# powerboard_monitor.net
KiCad netlist of a schematic drawn in EAGLE
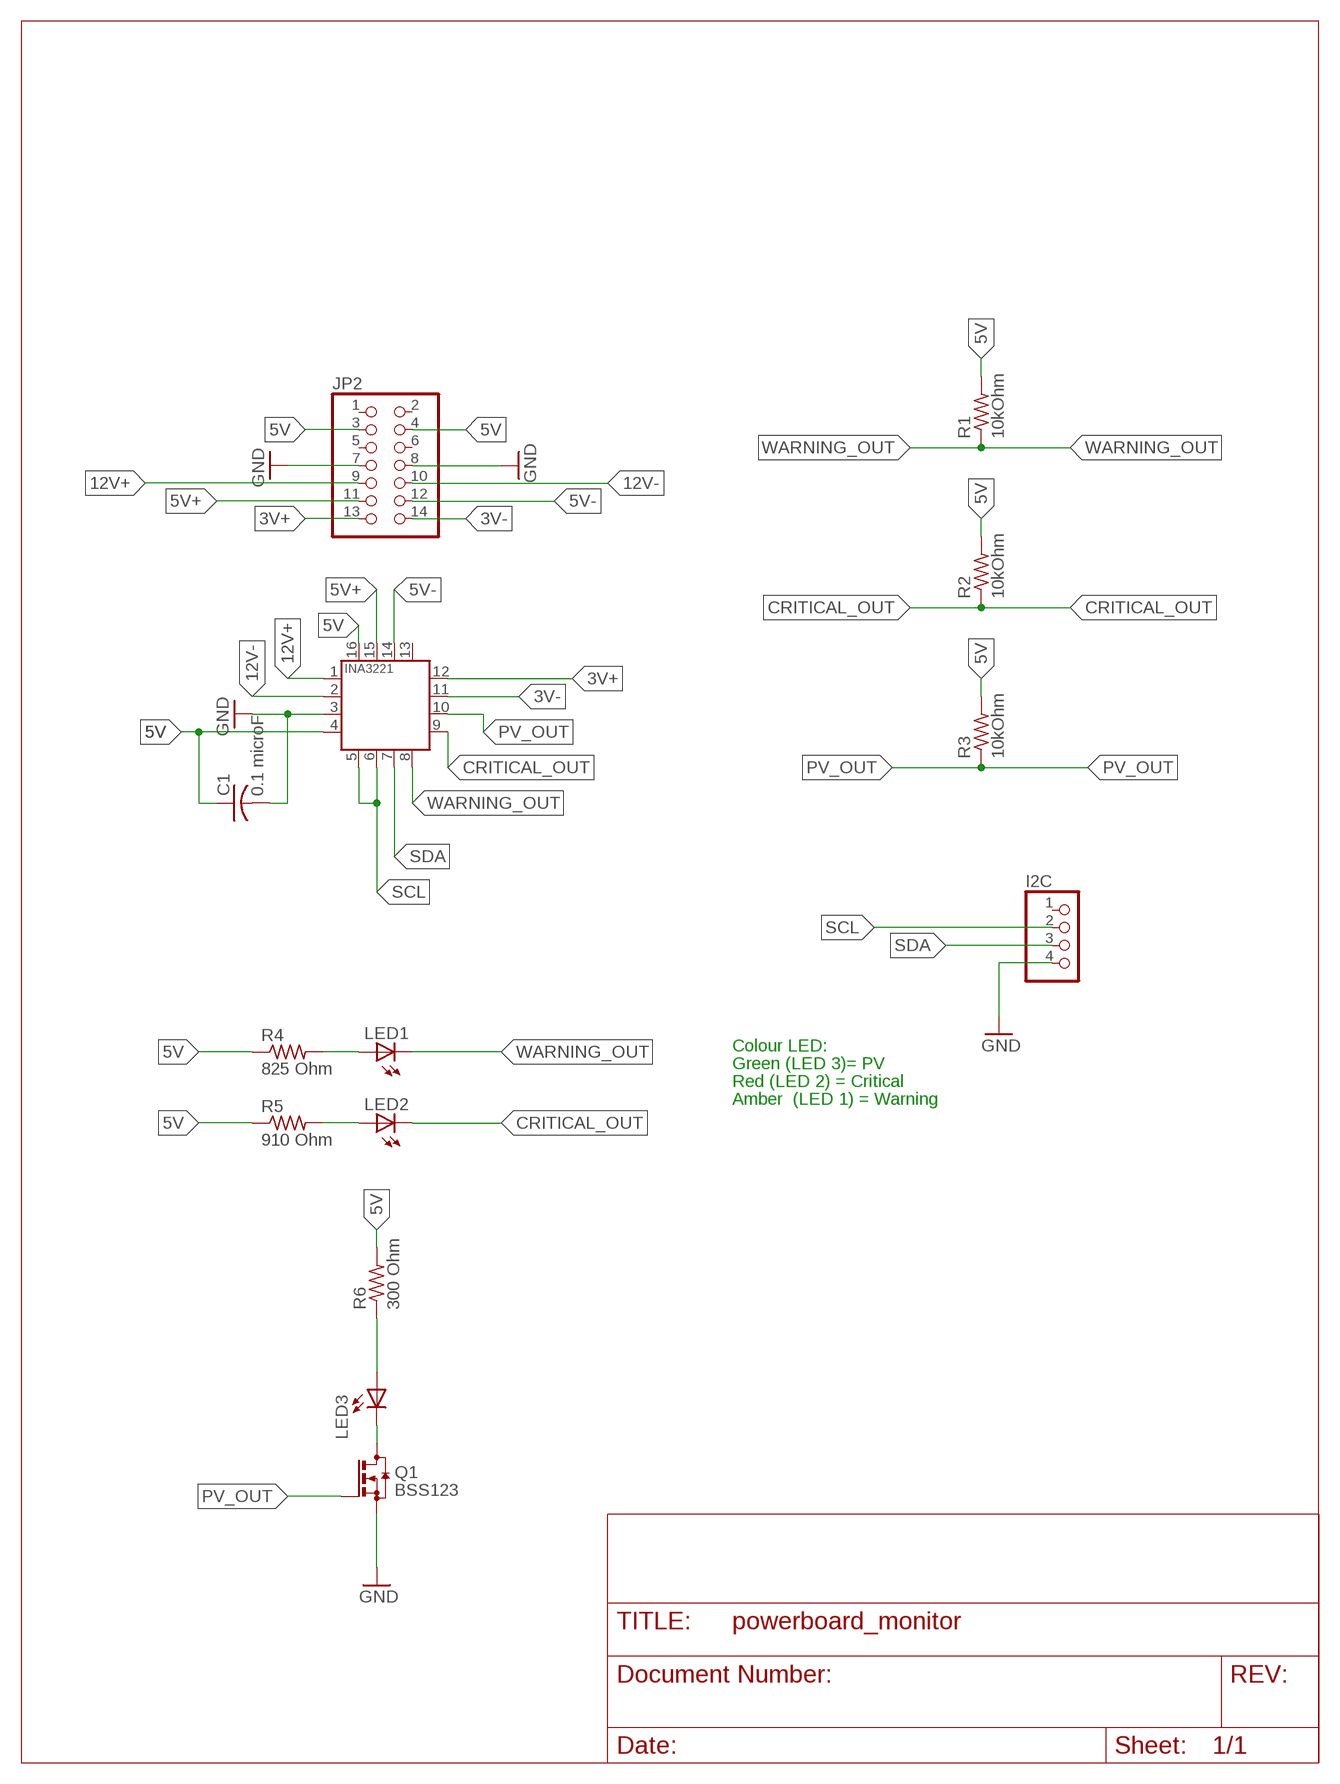
[diagram p0: schematic, sheet 1]

(export (version "E")
  (design (tool "Eeschema 10.0.6"))
  (components
    (comp (ref "C1")
      (value "0.1 microF")
      (footprint "eagle-import:C1206")
      (libsource (lib "eagle-import") (part "C-USC1206"))
    )
    (comp (ref "I2C")
      (value "PINHD-1X4")
      (footprint "eagle-import:1X04")
      (libsource (lib "eagle-import") (part "PINHD-1X4"))
    )
    (comp (ref "JP2")
      (value "PINHD-2X7")
      (footprint "eagle-import:2X07")
      (libsource (lib "eagle-import") (part "PINHD-2X7"))
    )
    (comp (ref "LED1")
      (value "LEDSMT1206")
      (footprint "eagle-import:1206")
      (libsource (lib "eagle-import") (part "LEDSMT1206"))
    )
    (comp (ref "LED2")
      (value "LEDSMT1206")
      (footprint "eagle-import:1206")
      (libsource (lib "eagle-import") (part "LEDSMT1206"))
    )
    (comp (ref "LED3")
      (value "LEDSMT1206")
      (footprint "eagle-import:1206")
      (libsource (lib "eagle-import") (part "LEDSMT1206"))
    )
    (comp (ref "Q1")
      (value "BSS123")
      (footprint "eagle-import:SOT23")
      (libsource (lib "eagle-import") (part "BSS123"))
    )
    (comp (ref "R1")
      (value "10kOhm")
      (footprint "eagle-import:R1206")
      (libsource (lib "eagle-import") (part "R-US_R1206"))
    )
    (comp (ref "R2")
      (value "10kOhm")
      (footprint "eagle-import:R1206")
      (libsource (lib "eagle-import") (part "R-US_R1206"))
    )
    (comp (ref "R3")
      (value "10kOhm")
      (footprint "eagle-import:R1206")
      (libsource (lib "eagle-import") (part "R-US_R1206"))
    )
    (comp (ref "R4")
      (value "825 Ohm")
      (footprint "eagle-import:R1206")
      (libsource (lib "eagle-import") (part "R-US_R1206"))
    )
    (comp (ref "R5")
      (value "910 Ohm")
      (footprint "eagle-import:R1206")
      (libsource (lib "eagle-import") (part "R-US_R1206"))
    )
    (comp (ref "R6")
      (value "300 Ohm")
      (footprint "eagle-import:R1206")
      (libsource (lib "eagle-import") (part "R-US_R1206"))
    )
    (comp (ref "U1")
      (value "INA3221.")
      (footprint "eagle-import:HVQFN16_4X4")
      (libsource (lib "eagle-import") (part "INA3221."))
    )
  )
  (nets
    (net (code "1") (name "3V+") (class "Default")
      (node (ref "JP2") (pin "13") (pinfunction "13_13") (pintype "passive"))
      (node (ref "U1") (pin "12") (pinfunction "IN+1_12") (pintype "input"))
    )
    (net (code "2") (name "3V-") (class "Default")
      (node (ref "JP2") (pin "14") (pinfunction "14_14") (pintype "passive"))
      (node (ref "U1") (pin "11") (pinfunction "IN-1_11") (pintype "input"))
    )
    (net (code "3") (name "5V") (class "Default")
      (node (ref "C1") (pin "1") (pinfunction "1_1") (pintype "passive"))
      (node (ref "JP2") (pin "3") (pinfunction "3_3") (pintype "passive"))
      (node (ref "JP2") (pin "4") (pinfunction "4_4") (pintype "passive"))
      (node (ref "R1") (pin "2") (pinfunction "2_2") (pintype "passive"))
      (node (ref "R2") (pin "2") (pinfunction "2_2") (pintype "passive"))
      (node (ref "R3") (pin "2") (pinfunction "2_2") (pintype "passive"))
      (node (ref "R4") (pin "1") (pinfunction "1_1") (pintype "passive"))
      (node (ref "R5") (pin "1") (pinfunction "1_1") (pintype "passive"))
      (node (ref "R6") (pin "2") (pinfunction "2_2") (pintype "passive"))
      (node (ref "U1") (pin "16") (pinfunction "VPU_16") (pintype "input"))
      (node (ref "U1") (pin "4") (pinfunction "VS_4") (pintype "power_in"))
    )
    (net (code "4") (name "5V+") (class "Default")
      (node (ref "JP2") (pin "11") (pinfunction "11_11") (pintype "passive"))
      (node (ref "U1") (pin "15") (pinfunction "IN+2_15") (pintype "input"))
    )
    (net (code "5") (name "5V-") (class "Default")
      (node (ref "JP2") (pin "12") (pinfunction "12_12") (pintype "passive"))
      (node (ref "U1") (pin "14") (pinfunction "IN-2_14") (pintype "input"))
    )
    (net (code "6") (name "12V+") (class "Default")
      (node (ref "JP2") (pin "9") (pinfunction "9_9") (pintype "passive"))
      (node (ref "U1") (pin "1") (pinfunction "IN-3_1") (pintype "input"))
    )
    (net (code "7") (name "12V-") (class "Default")
      (node (ref "JP2") (pin "10") (pinfunction "10_10") (pintype "passive"))
      (node (ref "U1") (pin "2") (pinfunction "IN+3_2") (pintype "input"))
    )
    (net (code "8") (name "CRITICAL_OUT") (class "Default")
      (node (ref "LED2") (pin "C") (pinfunction "C_C") (pintype "passive"))
      (node (ref "R2") (pin "1") (pinfunction "1_1") (pintype "passive"))
      (node (ref "U1") (pin "9") (pinfunction "CRITICAL_9") (pintype "output"))
    )
    (net (code "9") (name "GND") (class "Default")
      (node (ref "C1") (pin "2") (pinfunction "2_2") (pintype "passive"))
      (node (ref "I2C") (pin "4") (pinfunction "4_4") (pintype "passive"))
      (node (ref "JP2") (pin "7") (pinfunction "7_7") (pintype "passive"))
      (node (ref "JP2") (pin "8") (pinfunction "8_8") (pintype "passive"))
      (node (ref "Q1") (pin "2") (pinfunction "S_2") (pintype "passive"))
      (node (ref "U1") (pin "3") (pinfunction "GND_3") (pintype "power_in"))
    )
    (net (code "10") (name "Net-(LED1-PadA)") (class "Default")
      (node (ref "LED1") (pin "A") (pinfunction "A_A") (pintype "passive"))
      (node (ref "R4") (pin "2") (pinfunction "2_2") (pintype "passive"))
    )
    (net (code "11") (name "Net-(LED2-PadA)") (class "Default")
      (node (ref "LED2") (pin "A") (pinfunction "A_A") (pintype "passive"))
      (node (ref "R5") (pin "2") (pinfunction "2_2") (pintype "passive"))
    )
    (net (code "12") (name "Net-(LED3-PadA)") (class "Default")
      (node (ref "LED3") (pin "A") (pinfunction "A_A") (pintype "passive"))
      (node (ref "R6") (pin "1") (pinfunction "1_1") (pintype "passive"))
    )
    (net (code "13") (name "Net-(Q1-D)") (class "Default")
      (node (ref "LED3") (pin "C") (pinfunction "C_C") (pintype "passive"))
      (node (ref "Q1") (pin "3") (pinfunction "D_3") (pintype "passive"))
    )
    (net (code "14") (name "PV_OUT") (class "Default")
      (node (ref "Q1") (pin "1") (pinfunction "G_1") (pintype "passive"))
      (node (ref "R3") (pin "1") (pinfunction "1_1") (pintype "passive"))
      (node (ref "U1") (pin "10") (pinfunction "PV_10") (pintype "output"))
    )
    (net (code "15") (name "SCL") (class "Default")
      (node (ref "I2C") (pin "2") (pinfunction "2_2") (pintype "passive"))
      (node (ref "U1") (pin "5") (pinfunction "A0_5") (pintype "input"))
      (node (ref "U1") (pin "6") (pinfunction "SCL_6") (pintype "input"))
    )
    (net (code "16") (name "SDA") (class "Default")
      (node (ref "I2C") (pin "3") (pinfunction "3_3") (pintype "passive"))
      (node (ref "U1") (pin "7") (pinfunction "SDA_7") (pintype "bidirectional"))
    )
    (net (code "17") (name "WARNING_OUT") (class "Default")
      (node (ref "LED1") (pin "C") (pinfunction "C_C") (pintype "passive"))
      (node (ref "R1") (pin "1") (pinfunction "1_1") (pintype "passive"))
      (node (ref "U1") (pin "8") (pinfunction "WARNING_8") (pintype "output"))
    )
    (net (code "18") (name "unconnected-(I2C-Pad1)") (class "Default")
      (node (ref "I2C") (pin "1") (pinfunction "1_1") (pintype "passive"))
    )
    (net (code "19") (name "unconnected-(JP2-Pad1)") (class "Default")
      (node (ref "JP2") (pin "1") (pinfunction "1_1") (pintype "passive"))
    )
    (net (code "20") (name "unconnected-(JP2-Pad2)") (class "Default")
      (node (ref "JP2") (pin "2") (pinfunction "2_2") (pintype "passive"))
    )
    (net (code "21") (name "unconnected-(JP2-Pad5)") (class "Default")
      (node (ref "JP2") (pin "5") (pinfunction "5_5") (pintype "passive"))
    )
    (net (code "22") (name "unconnected-(JP2-Pad6)") (class "Default")
      (node (ref "JP2") (pin "6") (pinfunction "6_6") (pintype "passive"))
    )
    (net (code "23") (name "unconnected-(U1-TC-Pad13)") (class "Default")
      (node (ref "U1") (pin "13") (pinfunction "TC_13") (pintype "output"))
    )
  )
)
